# Level_Shifter.net
KiCad netlist of a schematic drawn in Altium Designer
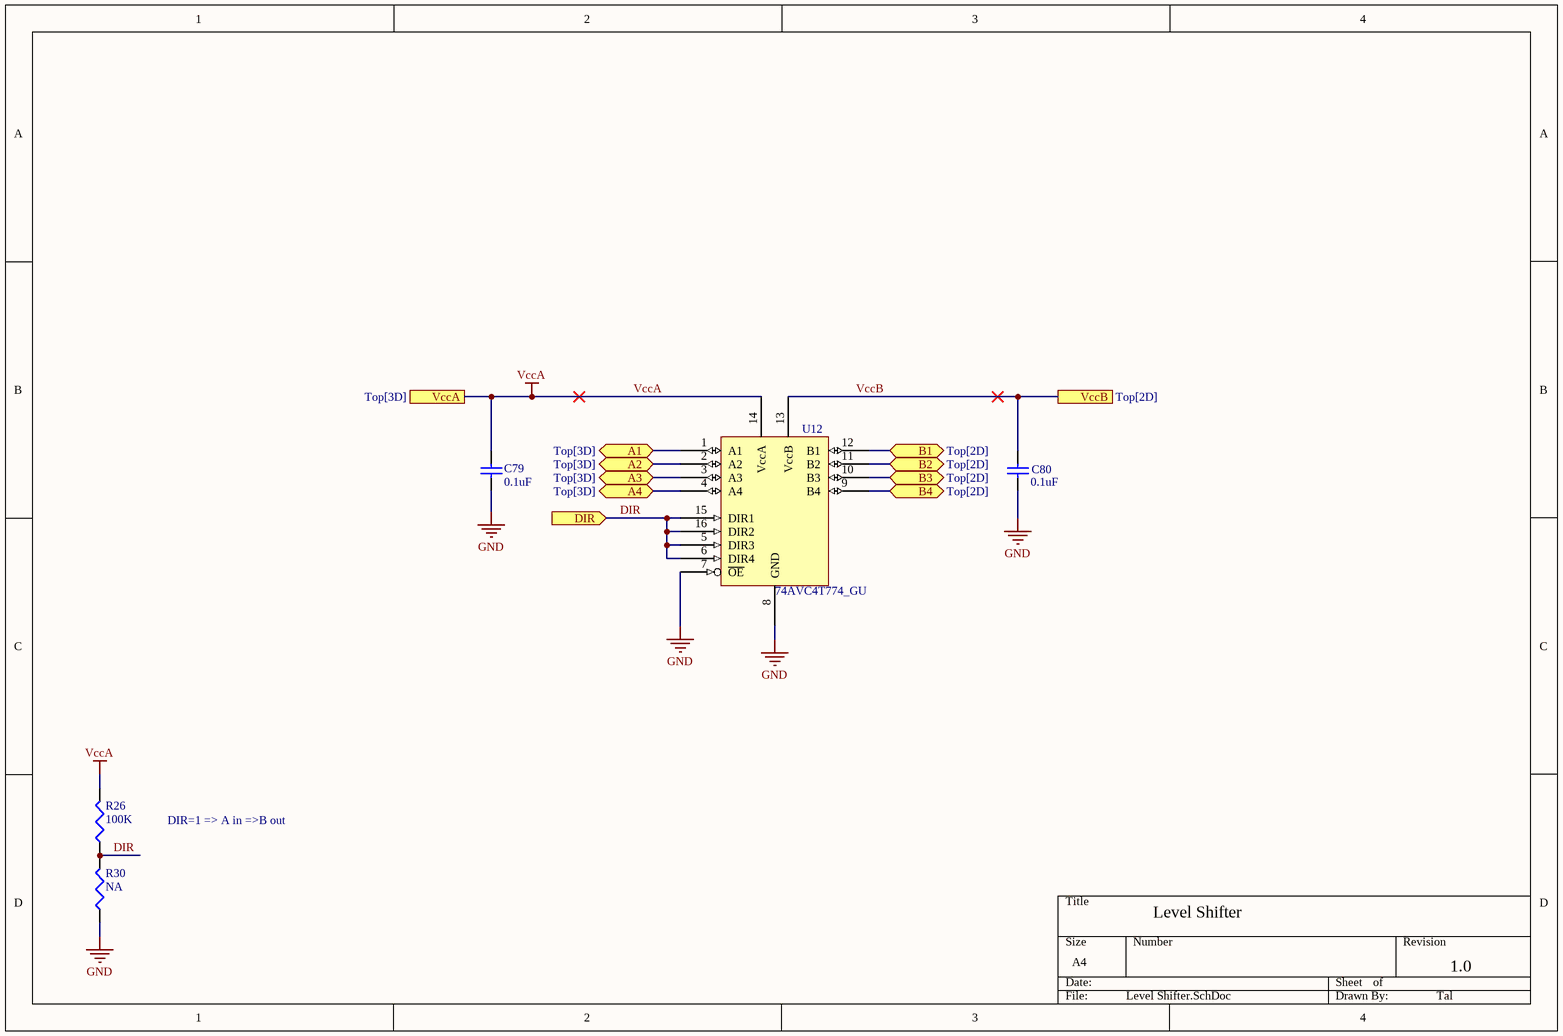
[diagram p0: Level Shifter.SchDoc]

(export (version "E")
  (design (tool "Eeschema 10.0.6"))
  (components
    (comp (ref "C79")
      (value "0.1uF 50V")
      (footprint "Landa_PCB:C0402")
      (description "CAP CER 0.1uF 50V NP0 0402")
      (fields
        (field (name "MANUFACTURER PART NUMBER") "C1005C0G1H6R8D")
        (field (name "MANUFACTURER") "TDK Corporation")
        (field (name "CAPACITANCE") "0.1uF")
      )
      (libsource (lib "L_SCH_C") (part "CAP CER 6.8pF 50V NP0 0402"))
    )
    (comp (ref "C80")
      (value "0.1uF 50V")
      (footprint "Landa_PCB:C0402")
      (description "CAP CER 0.1uF 50V NP0 0402")
      (fields
        (field (name "MANUFACTURER PART NUMBER") "C1005C0G1H6R8D")
        (field (name "MANUFACTURER") "TDK Corporation")
        (field (name "CAPACITANCE") "0.1uF")
      )
      (libsource (lib "L_SCH_C") (part "CAP CER 6.8pF 50V NP0 0402"))
    )
    (comp (ref "R26")
      (value "100K")
      (footprint "Landa_PCB:R0402")
      (description "RES 100K OHM 1/16W 1% 0402")
      (fields
        (field (name "MANUFACTURER PART NUMBER") "RMCF0402FT3K09")
        (field (name "MANUFACTURER") "Stackpole Electronics Inc")
      )
      (libsource (lib "L_SCH_R") (part "RES 3.09K OHM 1/16W 1% 0402"))
    )
    (comp (ref "R30")
      (value "NA")
      (footprint "Landa_PCB:R0402")
      (description "RES 3.09K OHM 1/16W 1% 0402")
      (fields
        (field (name "MANUFACTURER PART NUMBER") "RMCF0402FT3K09")
        (field (name "MANUFACTURER") "Stackpole Electronics Inc")
      )
      (libsource (lib "L_SCH_R") (part "RES 3.09K OHM 1/16W 1% 0402"))
    )
    (comp (ref "U12")
      (value "74AVC4T774_GU")
      (footprint "NXP_74AVC4T245GU,115")
      (libsource (lib "74AVC4T774_GU") (part "74AVC4T774_GU"))
    )
  )
  (nets
    (net (code "1") (name "/A1") (class "Default")
      (node (ref "U12") (pin "1") (pinfunction "A1_1") (pintype "bidirectional"))
    )
    (net (code "2") (name "/A2") (class "Default")
      (node (ref "U12") (pin "2") (pinfunction "A2_2") (pintype "bidirectional"))
    )
    (net (code "3") (name "/A3") (class "Default")
      (node (ref "U12") (pin "3") (pinfunction "A3_3") (pintype "bidirectional"))
    )
    (net (code "4") (name "/A4") (class "Default")
      (node (ref "U12") (pin "4") (pinfunction "A4_4") (pintype "bidirectional"))
    )
    (net (code "5") (name "/B1") (class "Default")
      (node (ref "U12") (pin "12") (pinfunction "B1_12") (pintype "bidirectional"))
    )
    (net (code "6") (name "/B2") (class "Default")
      (node (ref "U12") (pin "11") (pinfunction "B2_11") (pintype "bidirectional"))
    )
    (net (code "7") (name "/B3") (class "Default")
      (node (ref "U12") (pin "10") (pinfunction "B3_10") (pintype "bidirectional"))
    )
    (net (code "8") (name "/B4") (class "Default")
      (node (ref "U12") (pin "9") (pinfunction "B4_9") (pintype "bidirectional"))
    )
    (net (code "9") (name "/DIR") (class "Default")
      (node (ref "R26") (pin "1") (pinfunction "1_1") (pintype "passive"))
      (node (ref "R30") (pin "2") (pinfunction "2_2") (pintype "passive"))
      (node (ref "U12") (pin "15") (pinfunction "DIR1_15") (pintype "input"))
      (node (ref "U12") (pin "16") (pinfunction "DIR2_16") (pintype "input"))
      (node (ref "U12") (pin "5") (pinfunction "DIR3_5") (pintype "input"))
      (node (ref "U12") (pin "6") (pinfunction "DIR4_6") (pintype "input"))
    )
    (net (code "10") (name "/VccB") (class "Default")
      (node (ref "C80") (pin "2") (pinfunction "2_2") (pintype "passive"))
      (node (ref "U12") (pin "13") (pinfunction "VccB_13") (pintype "power_in"))
    )
    (net (code "11") (name "GND") (class "Default")
      (node (ref "C79") (pin "1") (pinfunction "1_1") (pintype "passive"))
      (node (ref "C80") (pin "1") (pinfunction "1_1") (pintype "passive"))
      (node (ref "R30") (pin "1") (pinfunction "1_1") (pintype "passive"))
      (node (ref "U12") (pin "7") (pinfunction "~{OE}_7") (pintype "input"))
      (node (ref "U12") (pin "8") (pinfunction "GND_8") (pintype "power_in"))
    )
    (net (code "12") (name "VccA") (class "Default")
      (node (ref "C79") (pin "2") (pinfunction "2_2") (pintype "passive"))
      (node (ref "R26") (pin "2") (pinfunction "2_2") (pintype "passive"))
      (node (ref "U12") (pin "14") (pinfunction "VccA_14") (pintype "power_in"))
    )
  )
)
